# SK3000v3_-_FINAL.net
KiCad netlist of a schematic drawn in EAGLE
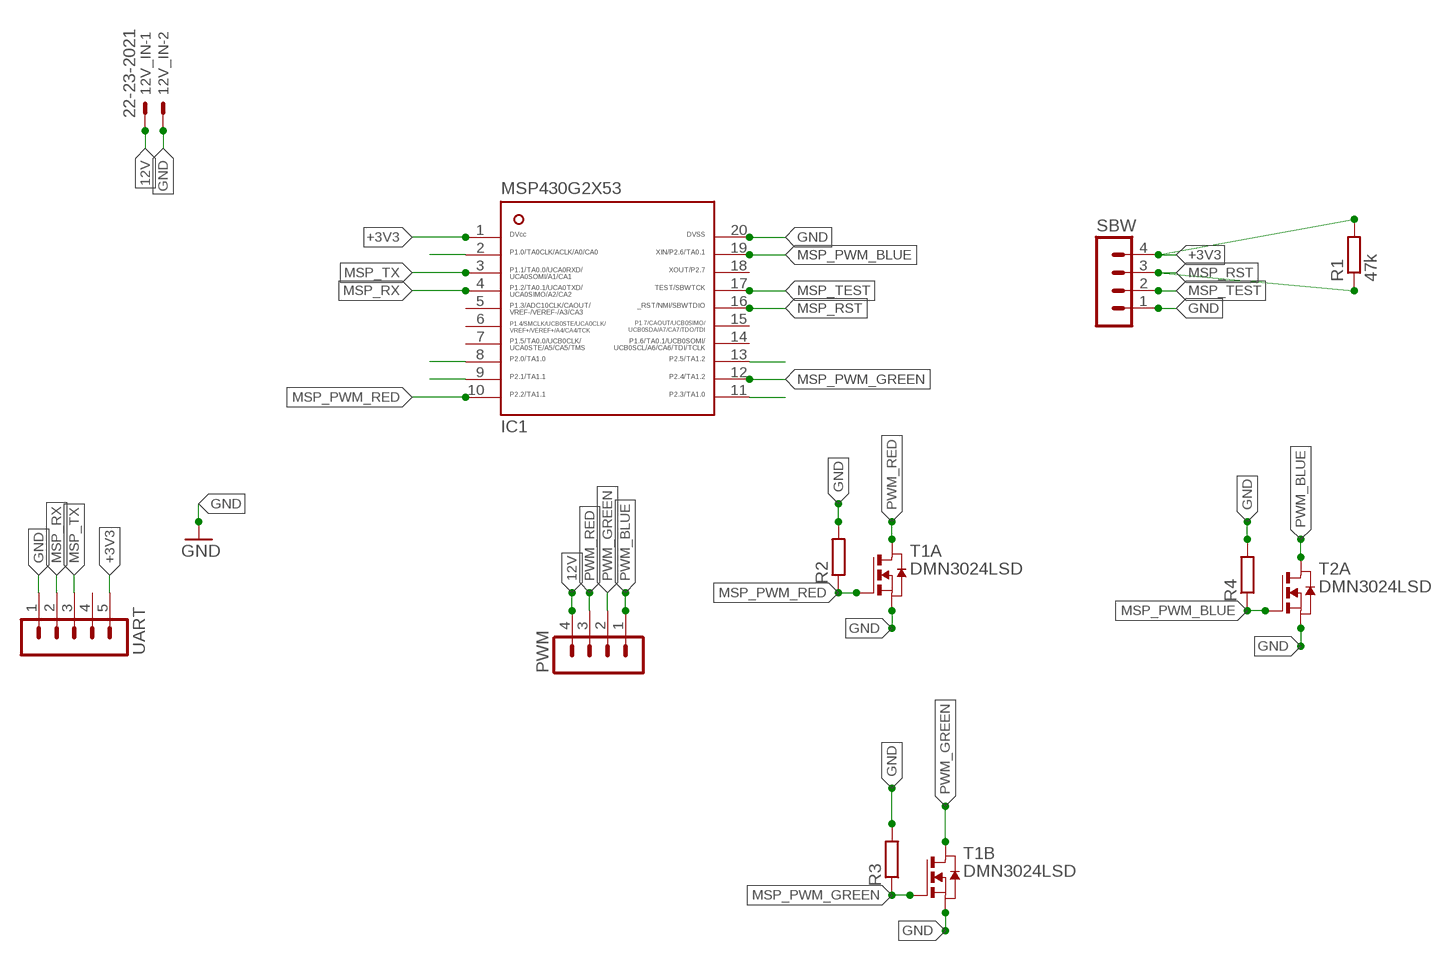
[diagram p0: schematic, sheet 1]

(export (version "E")
  (design (tool "Eeschema 10.0.6"))
  (components
    (comp (ref "12V_IN")
      (value "22-23-2021")
      (footprint "eagle-import:22-23-2021")
      (fields (field (name "MF") "MOLEX"))
      (libsource (lib "eagle-import") (part "22-23-2021"))
    )
    (comp (ref "IC1")
      (value "MSP430G2553")
      (footprint "eagle-import:PW20")
      (libsource (lib "eagle-import") (part "MSP430G2X53-20PW20"))
    )
    (comp (ref "PWM")
      (value "MA04-1")
      (footprint "eagle-import:MA04-1")
      (libsource (lib "eagle-import") (part "MA04-1"))
    )
    (comp (ref "R1")
      (value "47k")
      (footprint "eagle-import:0207_5V")
      (libsource (lib "eagle-import") (part "R-EU_0207/5V"))
    )
    (comp (ref "R2")
      (value "R-EU_0207/5V")
      (footprint "eagle-import:0207_5V")
      (libsource (lib "eagle-import") (part "R-EU_0207/5V"))
    )
    (comp (ref "R3")
      (value "R-EU_0207/5V")
      (footprint "eagle-import:0207_5V")
      (libsource (lib "eagle-import") (part "R-EU_0207/5V"))
    )
    (comp (ref "R4")
      (value "R-EU_0207/5V")
      (footprint "eagle-import:0207_5V")
      (libsource (lib "eagle-import") (part "R-EU_0207/5V"))
    )
    (comp (ref "SBW")
      (value "MA04-1")
      (footprint "eagle-import:MA04-1")
      (libsource (lib "eagle-import") (part "MA04-1"))
    )
    (comp (ref "T1")
      (value "DMN3024LSD")
      (footprint "eagle-import:SO8")
      (libsource (lib "eagle-import") (part "DMN3024LSD"))
    )
    (comp (ref "T2")
      (value "DMN3024LSD")
      (footprint "eagle-import:SO8")
      (libsource (lib "eagle-import") (part "DMN3024LSD"))
    )
    (comp (ref "UART")
      (value "MA05-1")
      (footprint "eagle-import:MA05-1")
      (libsource (lib "eagle-import") (part "MA05-1"))
    )
  )
  (nets
    (net (code "1") (name "+3V3") (class "Default")
      (node (ref "IC1") (pin "1") (pinfunction "1_1") (pintype "bidirectional"))
      (node (ref "R1") (pin "2") (pinfunction "2_2") (pintype "passive"))
      (node (ref "SBW") (pin "4") (pinfunction "4_4") (pintype "passive"))
      (node (ref "UART") (pin "5") (pinfunction "5_5") (pintype "passive"))
    )
    (net (code "2") (name "12V") (class "Default")
      (node (ref "12V_IN") (pin "1") (pinfunction "S_1") (pintype "passive"))
      (node (ref "PWM") (pin "4") (pinfunction "4_4") (pintype "passive"))
    )
    (net (code "3") (name "GND") (class "Default")
      (node (ref "12V_IN") (pin "2") (pinfunction "S_2") (pintype "passive"))
      (node (ref "IC1") (pin "20") (pinfunction "20_20") (pintype "bidirectional"))
      (node (ref "R2") (pin "2") (pinfunction "2_2") (pintype "passive"))
      (node (ref "R3") (pin "2") (pinfunction "2_2") (pintype "passive"))
      (node (ref "R4") (pin "2") (pinfunction "2_2") (pintype "passive"))
      (node (ref "SBW") (pin "1") (pinfunction "1_1") (pintype "passive"))
      (node (ref "T1") (pin "1") (pinfunction "S_1") (pintype "passive"))
      (node (ref "T1") (pin "3") (pinfunction "S_3") (pintype "passive"))
      (node (ref "T2") (pin "1") (pinfunction "S_1") (pintype "passive"))
      (node (ref "UART") (pin "1") (pinfunction "1_1") (pintype "passive"))
    )
    (net (code "4") (name "MSP_PWM_BLUE") (class "Default")
      (node (ref "IC1") (pin "19") (pinfunction "19_19") (pintype "bidirectional"))
      (node (ref "R4") (pin "1") (pinfunction "1_1") (pintype "passive"))
      (node (ref "T2") (pin "2") (pinfunction "G_2") (pintype "passive"))
    )
    (net (code "5") (name "MSP_PWM_GREEN") (class "Default")
      (node (ref "IC1") (pin "12") (pinfunction "12_12") (pintype "bidirectional"))
      (node (ref "R3") (pin "1") (pinfunction "1_1") (pintype "passive"))
      (node (ref "T1") (pin "4") (pinfunction "G_4") (pintype "passive"))
    )
    (net (code "6") (name "MSP_PWM_RED") (class "Default")
      (node (ref "IC1") (pin "10") (pinfunction "10_10") (pintype "bidirectional"))
      (node (ref "R2") (pin "1") (pinfunction "1_1") (pintype "passive"))
      (node (ref "T1") (pin "2") (pinfunction "G_2") (pintype "passive"))
    )
    (net (code "7") (name "MSP_RST") (class "Default")
      (node (ref "IC1") (pin "16") (pinfunction "16_16") (pintype "bidirectional"))
      (node (ref "R1") (pin "1") (pinfunction "1_1") (pintype "passive"))
      (node (ref "SBW") (pin "3") (pinfunction "3_3") (pintype "passive"))
    )
    (net (code "8") (name "MSP_RX") (class "Default")
      (node (ref "IC1") (pin "4") (pinfunction "4_4") (pintype "bidirectional"))
      (node (ref "UART") (pin "2") (pinfunction "2_2") (pintype "passive"))
    )
    (net (code "9") (name "MSP_TEST") (class "Default")
      (node (ref "IC1") (pin "17") (pinfunction "17_17") (pintype "bidirectional"))
      (node (ref "SBW") (pin "2") (pinfunction "2_2") (pintype "passive"))
    )
    (net (code "10") (name "MSP_TX") (class "Default")
      (node (ref "IC1") (pin "3") (pinfunction "3_3") (pintype "bidirectional"))
      (node (ref "UART") (pin "3") (pinfunction "3_3") (pintype "passive"))
    )
    (net (code "11") (name "PWM_BLUE") (class "Default")
      (node (ref "PWM") (pin "1") (pinfunction "1_1") (pintype "passive"))
      (node (ref "T2") (pin "7") (pinfunction "D_7") (pintype "passive"))
      (node (ref "T2") (pin "8") (pinfunction "D_8") (pintype "passive"))
    )
    (net (code "12") (name "PWM_GREEN") (class "Default")
      (node (ref "PWM") (pin "2") (pinfunction "2_2") (pintype "passive"))
      (node (ref "T1") (pin "5") (pinfunction "D_5") (pintype "passive"))
      (node (ref "T1") (pin "6") (pinfunction "D_6") (pintype "passive"))
    )
    (net (code "13") (name "PWM_RED") (class "Default")
      (node (ref "PWM") (pin "3") (pinfunction "3_3") (pintype "passive"))
      (node (ref "T1") (pin "7") (pinfunction "D_7") (pintype "passive"))
      (node (ref "T1") (pin "8") (pinfunction "D_8") (pintype "passive"))
    )
    (net (code "14") (name "unconnected-(IC1-Pad2)") (class "Default")
      (node (ref "IC1") (pin "2") (pinfunction "2_2") (pintype "bidirectional"))
    )
    (net (code "15") (name "unconnected-(IC1-Pad5)") (class "Default")
      (node (ref "IC1") (pin "5") (pinfunction "5_5") (pintype "bidirectional"))
    )
    (net (code "16") (name "unconnected-(IC1-Pad6)") (class "Default")
      (node (ref "IC1") (pin "6") (pinfunction "6_6") (pintype "bidirectional"))
    )
    (net (code "17") (name "unconnected-(IC1-Pad7)") (class "Default")
      (node (ref "IC1") (pin "7") (pinfunction "7_7") (pintype "bidirectional"))
    )
    (net (code "18") (name "unconnected-(IC1-Pad8)") (class "Default")
      (node (ref "IC1") (pin "8") (pinfunction "8_8") (pintype "bidirectional"))
    )
    (net (code "19") (name "unconnected-(IC1-Pad9)") (class "Default")
      (node (ref "IC1") (pin "9") (pinfunction "9_9") (pintype "bidirectional"))
    )
    (net (code "20") (name "unconnected-(IC1-Pad11)") (class "Default")
      (node (ref "IC1") (pin "11") (pinfunction "11_11") (pintype "bidirectional"))
    )
    (net (code "21") (name "unconnected-(IC1-Pad13)") (class "Default")
      (node (ref "IC1") (pin "13") (pinfunction "13_13") (pintype "bidirectional"))
    )
    (net (code "22") (name "unconnected-(IC1-Pad14)") (class "Default")
      (node (ref "IC1") (pin "14") (pinfunction "14_14") (pintype "bidirectional"))
    )
    (net (code "23") (name "unconnected-(IC1-Pad15)") (class "Default")
      (node (ref "IC1") (pin "15") (pinfunction "15_15") (pintype "bidirectional"))
    )
    (net (code "24") (name "unconnected-(IC1-Pad18)") (class "Default")
      (node (ref "IC1") (pin "18") (pinfunction "18_18") (pintype "bidirectional"))
    )
    (net (code "25") (name "unconnected-(UART-Pad4)") (class "Default")
      (node (ref "UART") (pin "4") (pinfunction "4_4") (pintype "passive"))
    )
  )
)
